# limiter.net
KiCad netlist of a schematic drawn in Altium Designer
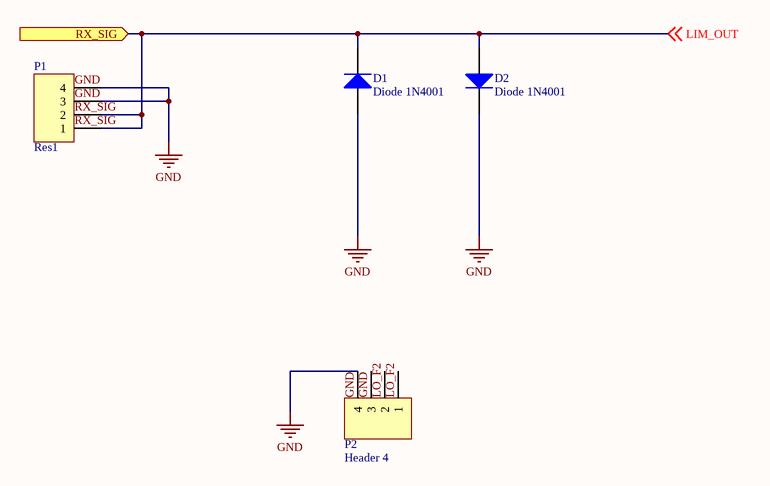
[diagram p0: limiter.SchDoc]

(export (version "E")
  (design (tool "Eeschema 10.0.6"))
  (components
    (comp (ref "D1")
      (value "Diode 1N4001")
      (footprint "DO-41")
      (description "1 Amp General Purpose Rectifier")
      (fields (field (name "PUBLISHER") "Altium Limited"))
      (libsource (lib "Miscellaneous Devices") (part "Diode 1N4001"))
    )
    (comp (ref "D2")
      (value "Diode 1N4001")
      (footprint "DO-41")
      (description "1 Amp General Purpose Rectifier")
      (fields (field (name "PUBLISHER") "Altium Limited"))
      (libsource (lib "Miscellaneous Devices") (part "Diode 1N4001"))
    )
    (comp (ref "P1")
      (value "Res1")
      (footprint "HDR1X4")
      (description "Header, 4-Pin")
      (fields (field (name "PUBLISHER") "Altium Limited"))
      (libsource (lib "") (part "Header 4_1"))
    )
    (comp (ref "P2")
      (value "Header 4")
      (footprint "HDR1X4")
      (description "Header, 4-Pin")
      (fields (field (name "PUBLISHER") "Altium Limited"))
      (libsource (lib "Miscellaneous Connectors") (part "Header 4"))
    )
  )
  (nets
    (net (code "2") (name "GND") (class "Default")
      (node (ref "D1") (pin "1") (pinfunction "A_1") (pintype "passive"))
      (node (ref "D2") (pin "2") (pinfunction "K_2") (pintype "passive"))
      (node (ref "P1") (pin "3") (pinfunction "3_3") (pintype "passive"))
      (node (ref "P1") (pin "4") (pinfunction "4_4") (pintype "passive"))
      (node (ref "P2") (pin "4") (pinfunction "4_4") (pintype "passive"))
    )
    (net (code "3") (name "LIM_OUT") (class "Default")
      (node (ref "D1") (pin "2") (pinfunction "K_2") (pintype "passive"))
      (node (ref "D2") (pin "1") (pinfunction "A_1") (pintype "passive"))
      (node (ref "P1") (pin "1") (pinfunction "1_1") (pintype "passive"))
      (node (ref "P1") (pin "2") (pinfunction "2_2") (pintype "passive"))
    )
    (net (code "4") (name "unconnected-(P2-Pad1)") (class "Default")
      (node (ref "P2") (pin "1") (pinfunction "1_1") (pintype "passive"))
    )
    (net (code "5") (name "unconnected-(P2-Pad2)") (class "Default")
      (node (ref "P2") (pin "2") (pinfunction "2_2") (pintype "passive"))
    )
    (net (code "6") (name "unconnected-(P2-Pad3)") (class "Default")
      (node (ref "P2") (pin "3") (pinfunction "3_3") (pintype "passive"))
    )
  )
)
